# Encoder_AS5145B.net
KiCad netlist of a schematic drawn in EAGLE
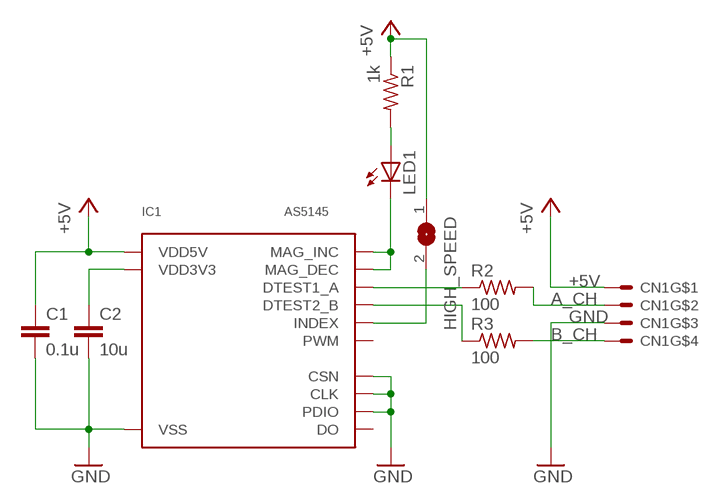
[diagram p0: schematic, sheet 1]

(export (version "E")
  (design (tool "Eeschema 10.0.6"))
  (components
    (comp (ref "C1")
      (value "0.1u")
      (footprint "eagle-import:C0603")
      (libsource (lib "eagle-import") (part "C-EUC0603"))
    )
    (comp (ref "C2")
      (value "10u")
      (footprint "eagle-import:C2012")
      (libsource (lib "eagle-import") (part "CC2012"))
    )
    (comp (ref "CN1")
      (value "4B-XH-AS4B")
      (footprint "eagle-import:S4B-XH-A")
      (libsource (lib "eagle-import") (part "4B-XH-AS4B"))
    )
    (comp (ref "HIGH_SPEED")
      (value "SJ")
      (footprint "eagle-import:SJ")
      (libsource (lib "eagle-import") (part "SJ"))
    )
    (comp (ref "IC1")
      (value "AS5145")
      (footprint "eagle-import:SSOP16-WIDE")
      (libsource (lib "eagle-import") (part "AS5145"))
    )
    (comp (ref "LED1")
      (value "LEDCHIPLED_0805")
      (footprint "eagle-import:CHIPLED_0805")
      (libsource (lib "eagle-import") (part "LEDCHIPLED_0805"))
    )
    (comp (ref "R1")
      (value "1k")
      (footprint "eagle-import:R1608")
      (libsource (lib "eagle-import") (part "R-US_R1608"))
    )
    (comp (ref "R2")
      (value "100")
      (footprint "eagle-import:R1608")
      (libsource (lib "eagle-import") (part "R-US_R1608"))
    )
    (comp (ref "R3")
      (value "100")
      (footprint "eagle-import:R1608")
      (libsource (lib "eagle-import") (part "R-US_R1608"))
    )
  )
  (nets
    (net (code "1") (name "+5V") (class "Default")
      (node (ref "C1") (pin "1") (pinfunction "1_1") (pintype "passive"))
      (node (ref "CN1") (pin "1") (pinfunction "S_1") (pintype "passive"))
      (node (ref "HIGH_SPEED") (pin "1") (pinfunction "1_1") (pintype "passive"))
      (node (ref "IC1") (pin "16") (pinfunction "VDD5V_16") (pintype "power_in"))
      (node (ref "R1") (pin "1") (pinfunction "1_1") (pintype "passive"))
    )
    (net (code "2") (name "/A_CH") (class "Default")
      (node (ref "CN1") (pin "2") (pinfunction "S_2") (pintype "passive"))
      (node (ref "R2") (pin "2") (pinfunction "2_2") (pintype "passive"))
    )
    (net (code "3") (name "/B_CH") (class "Default")
      (node (ref "CN1") (pin "4") (pinfunction "S_4") (pintype "passive"))
      (node (ref "R3") (pin "2") (pinfunction "2_2") (pintype "passive"))
    )
    (net (code "4") (name "GND") (class "Default")
      (node (ref "C1") (pin "2") (pinfunction "2_2") (pintype "passive"))
      (node (ref "C2") (pin "2") (pinfunction "2_2") (pintype "passive"))
      (node (ref "CN1") (pin "3") (pinfunction "S_3") (pintype "passive"))
      (node (ref "IC1") (pin "10") (pinfunction "CLK_10") (pintype "input"))
      (node (ref "IC1") (pin "11") (pinfunction "CSN_11") (pintype "input"))
      (node (ref "IC1") (pin "7") (pinfunction "VSS_7") (pintype "power_in"))
      (node (ref "IC1") (pin "8") (pinfunction "PDIO_8") (pintype "input"))
    )
    (net (code "5") (name "Net-(IC1-DTEST1_A)") (class "Default")
      (node (ref "IC1") (pin "3") (pinfunction "DTEST1_A_3") (pintype "output"))
      (node (ref "R2") (pin "1") (pinfunction "1_1") (pintype "passive"))
    )
    (net (code "6") (name "Net-(IC1-DTEST2_B)") (class "Default")
      (node (ref "IC1") (pin "4") (pinfunction "DTEST2_B_4") (pintype "output"))
      (node (ref "R3") (pin "1") (pinfunction "1_1") (pintype "passive"))
    )
    (net (code "7") (name "Net-(IC1-INDEX)") (class "Default")
      (node (ref "HIGH_SPEED") (pin "2") (pinfunction "2_2") (pintype "passive"))
      (node (ref "IC1") (pin "6") (pinfunction "INDEX_6") (pintype "output"))
    )
    (net (code "8") (name "Net-(IC1-MAG_DEC)") (class "Default")
      (node (ref "IC1") (pin "1") (pinfunction "MAG_INC_1") (pintype "open_collector"))
      (node (ref "IC1") (pin "2") (pinfunction "MAG_DEC_2") (pintype "open_collector"))
      (node (ref "LED1") (pin "C") (pinfunction "C_C") (pintype "passive"))
    )
    (net (code "9") (name "Net-(IC1-VDD3V3)") (class "Default")
      (node (ref "C2") (pin "1") (pinfunction "1_1") (pintype "passive"))
      (node (ref "IC1") (pin "15") (pinfunction "VDD3V3_15") (pintype "power_in"))
    )
    (net (code "10") (name "Net-(LED1-PadA)") (class "Default")
      (node (ref "LED1") (pin "A") (pinfunction "A_A") (pintype "passive"))
      (node (ref "R1") (pin "2") (pinfunction "2_2") (pintype "passive"))
    )
    (net (code "11") (name "unconnected-(IC1-DO-Pad9)") (class "Default")
      (node (ref "IC1") (pin "9") (pinfunction "DO_9") (pintype "output"))
    )
    (net (code "12") (name "unconnected-(IC1-NC1-Pad5)") (class "Default")
      (node (ref "IC1") (pin "5") (pinfunction "NC1_5") (pintype "no_connect"))
    )
    (net (code "13") (name "unconnected-(IC1-NC1-Pad13)") (class "Default")
      (node (ref "IC1") (pin "13") (pinfunction "NC1_13") (pintype "no_connect"))
    )
    (net (code "14") (name "unconnected-(IC1-NC1-Pad14)") (class "Default")
      (node (ref "IC1") (pin "14") (pinfunction "NC1_14") (pintype "no_connect"))
    )
    (net (code "15") (name "unconnected-(IC1-PWM-Pad12)") (class "Default")
      (node (ref "IC1") (pin "12") (pinfunction "PWM_12") (pintype "output"))
    )
  )
)
